# v0.net
KiCad netlist of a schematic drawn in EAGLE
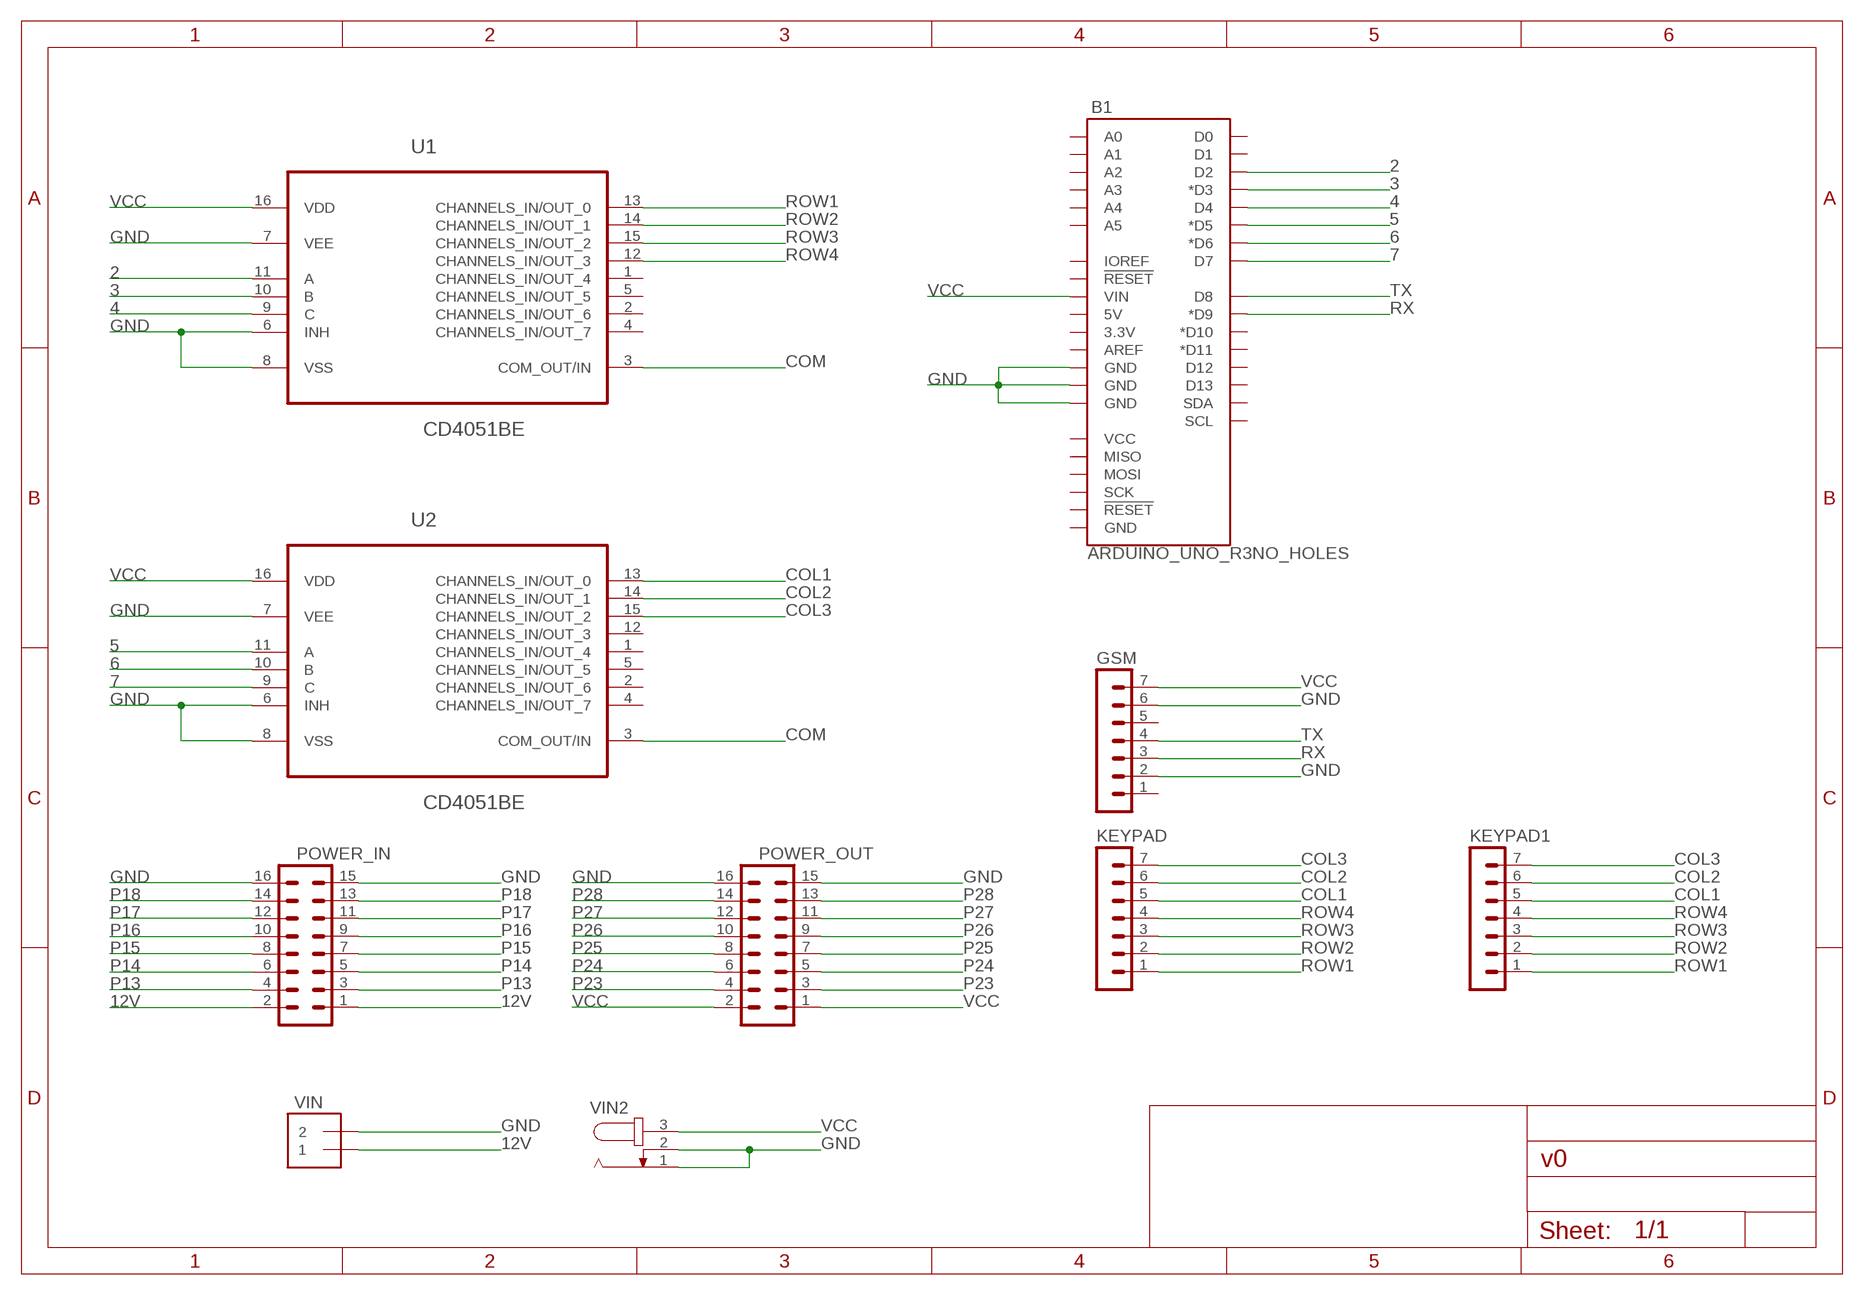
[diagram p0: schematic, sheet 1]

(export (version "E")
  (design (tool "Eeschema 10.0.6"))
  (components
    (comp (ref "B1")
      (value "ARDUINO_UNO_R3NO_HOLES")
      (footprint "eagle-import:ARDUINO_R3_NO_HOLES")
      (libsource (lib "eagle-import") (part "ARDUINO_UNO_R3NO_HOLES"))
    )
    (comp (ref "GSM")
      (value "MA07-1")
      (footprint "eagle-import:MA07-1")
      (libsource (lib "eagle-import") (part "MA07-1"))
    )
    (comp (ref "KEYPAD")
      (value "MA07-1")
      (footprint "eagle-import:MA07-1")
      (libsource (lib "eagle-import") (part "MA07-1"))
    )
    (comp (ref "KEYPAD1")
      (value "MA07-1")
      (footprint "eagle-import:MA07-1")
      (libsource (lib "eagle-import") (part "MA07-1"))
    )
    (comp (ref "POWER_IN")
      (value "MA08-2")
      (footprint "eagle-import:MA08-2")
      (libsource (lib "eagle-import") (part "MA08-2"))
    )
    (comp (ref "POWER_OUT")
      (value "MA08-2")
      (footprint "eagle-import:MA08-2")
      (libsource (lib "eagle-import") (part "MA08-2"))
    )
    (comp (ref "U1")
      (value "CD4051BE")
      (footprint "eagle-import:DIP254P762X508-16")
      (libsource (lib "eagle-import") (part "CD4051BE"))
    )
    (comp (ref "U2")
      (value "CD4051BE")
      (footprint "eagle-import:DIP254P762X508-16")
      (libsource (lib "eagle-import") (part "CD4051BE"))
    )
    (comp (ref "VIN")
      (value "1X2-3.5MM")
      (footprint "eagle-import:1X2-3.5MM")
      (libsource (lib "eagle-import") (part "1X2-3.5MM"))
    )
    (comp (ref "VIN2")
      (value "JACK-PLUG0")
      (footprint "eagle-import:SPC4077")
      (libsource (lib "eagle-import") (part "JACK-PLUG0"))
    )
  )
  (nets
    (net (code "1") (name "/2") (class "Default")
      (node (ref "B1") (pin "D2") (pinfunction "D2_D2") (pintype "bidirectional"))
      (node (ref "U1") (pin "11") (pinfunction "A_11") (pintype "input"))
    )
    (net (code "2") (name "/3") (class "Default")
      (node (ref "B1") (pin "D3") (pinfunction "*D3_D3") (pintype "bidirectional"))
      (node (ref "U1") (pin "10") (pinfunction "B_10") (pintype "input"))
    )
    (net (code "3") (name "/4") (class "Default")
      (node (ref "B1") (pin "D4") (pinfunction "D4_D4") (pintype "bidirectional"))
      (node (ref "U1") (pin "9") (pinfunction "C_9") (pintype "input"))
    )
    (net (code "4") (name "/5") (class "Default")
      (node (ref "B1") (pin "D5") (pinfunction "*D5_D5") (pintype "bidirectional"))
      (node (ref "U2") (pin "11") (pinfunction "A_11") (pintype "input"))
    )
    (net (code "5") (name "/6") (class "Default")
      (node (ref "B1") (pin "D6") (pinfunction "*D6_D6") (pintype "bidirectional"))
      (node (ref "U2") (pin "10") (pinfunction "B_10") (pintype "input"))
    )
    (net (code "6") (name "/7") (class "Default")
      (node (ref "B1") (pin "D7") (pinfunction "D7_D7") (pintype "bidirectional"))
      (node (ref "U2") (pin "9") (pinfunction "C_9") (pintype "input"))
    )
    (net (code "7") (name "/12V") (class "Default")
      (node (ref "POWER_IN") (pin "1") (pinfunction "1_1") (pintype "passive"))
      (node (ref "POWER_IN") (pin "2") (pinfunction "2_2") (pintype "passive"))
      (node (ref "VIN") (pin "1") (pinfunction "1_1") (pintype "passive"))
    )
    (net (code "8") (name "/COL1") (class "Default")
      (node (ref "KEYPAD") (pin "5") (pinfunction "5_5") (pintype "passive"))
      (node (ref "KEYPAD1") (pin "5") (pinfunction "5_5") (pintype "passive"))
      (node (ref "U2") (pin "13") (pinfunction "CHANNELS_IN/OUT_0_13") (pintype "bidirectional"))
    )
    (net (code "9") (name "/COL2") (class "Default")
      (node (ref "KEYPAD") (pin "6") (pinfunction "6_6") (pintype "passive"))
      (node (ref "KEYPAD1") (pin "6") (pinfunction "6_6") (pintype "passive"))
      (node (ref "U2") (pin "14") (pinfunction "CHANNELS_IN/OUT_1_14") (pintype "bidirectional"))
    )
    (net (code "10") (name "/COL3") (class "Default")
      (node (ref "KEYPAD") (pin "7") (pinfunction "7_7") (pintype "passive"))
      (node (ref "KEYPAD1") (pin "7") (pinfunction "7_7") (pintype "passive"))
      (node (ref "U2") (pin "15") (pinfunction "CHANNELS_IN/OUT_2_15") (pintype "bidirectional"))
    )
    (net (code "11") (name "/COM") (class "Default")
      (node (ref "U1") (pin "3") (pinfunction "COM_OUT/IN_3") (pintype "bidirectional"))
      (node (ref "U2") (pin "3") (pinfunction "COM_OUT/IN_3") (pintype "bidirectional"))
    )
    (net (code "12") (name "/GND") (class "Default")
      (node (ref "B1") (pin "GND@2") (pinfunction "GND_GND@2") (pintype "bidirectional"))
      (node (ref "B1") (pin "GND@3") (pinfunction "GND_GND@3") (pintype "bidirectional"))
      (node (ref "B1") (pin "GND@4") (pinfunction "GND_GND@4") (pintype "bidirectional"))
      (node (ref "GSM") (pin "2") (pinfunction "2_2") (pintype "passive"))
      (node (ref "GSM") (pin "6") (pinfunction "6_6") (pintype "passive"))
      (node (ref "POWER_IN") (pin "15") (pinfunction "15_15") (pintype "passive"))
      (node (ref "POWER_IN") (pin "16") (pinfunction "16_16") (pintype "passive"))
      (node (ref "POWER_OUT") (pin "15") (pinfunction "15_15") (pintype "passive"))
      (node (ref "POWER_OUT") (pin "16") (pinfunction "16_16") (pintype "passive"))
      (node (ref "U1") (pin "6") (pinfunction "INH_6") (pintype "input"))
      (node (ref "U1") (pin "7") (pinfunction "VEE_7") (pintype "power_in"))
      (node (ref "U1") (pin "8") (pinfunction "VSS_8") (pintype "power_in"))
      (node (ref "U2") (pin "6") (pinfunction "INH_6") (pintype "input"))
      (node (ref "U2") (pin "7") (pinfunction "VEE_7") (pintype "power_in"))
      (node (ref "U2") (pin "8") (pinfunction "VSS_8") (pintype "power_in"))
      (node (ref "VIN") (pin "2") (pinfunction "2_2") (pintype "passive"))
      (node (ref "VIN2") (pin "1") (pinfunction "1_1") (pintype "passive"))
      (node (ref "VIN2") (pin "2") (pinfunction "2_2") (pintype "passive"))
    )
    (net (code "13") (name "/P13") (class "Default")
      (node (ref "POWER_IN") (pin "3") (pinfunction "3_3") (pintype "passive"))
      (node (ref "POWER_IN") (pin "4") (pinfunction "4_4") (pintype "passive"))
    )
    (net (code "14") (name "/P14") (class "Default")
      (node (ref "POWER_IN") (pin "5") (pinfunction "5_5") (pintype "passive"))
      (node (ref "POWER_IN") (pin "6") (pinfunction "6_6") (pintype "passive"))
    )
    (net (code "15") (name "/P15") (class "Default")
      (node (ref "POWER_IN") (pin "7") (pinfunction "7_7") (pintype "passive"))
      (node (ref "POWER_IN") (pin "8") (pinfunction "8_8") (pintype "passive"))
    )
    (net (code "16") (name "/P16") (class "Default")
      (node (ref "POWER_IN") (pin "10") (pinfunction "10_10") (pintype "passive"))
      (node (ref "POWER_IN") (pin "9") (pinfunction "9_9") (pintype "passive"))
    )
    (net (code "17") (name "/P17") (class "Default")
      (node (ref "POWER_IN") (pin "11") (pinfunction "11_11") (pintype "passive"))
      (node (ref "POWER_IN") (pin "12") (pinfunction "12_12") (pintype "passive"))
    )
    (net (code "18") (name "/P18") (class "Default")
      (node (ref "POWER_IN") (pin "13") (pinfunction "13_13") (pintype "passive"))
      (node (ref "POWER_IN") (pin "14") (pinfunction "14_14") (pintype "passive"))
    )
    (net (code "19") (name "/P23") (class "Default")
      (node (ref "POWER_OUT") (pin "3") (pinfunction "3_3") (pintype "passive"))
      (node (ref "POWER_OUT") (pin "4") (pinfunction "4_4") (pintype "passive"))
    )
    (net (code "20") (name "/P24") (class "Default")
      (node (ref "POWER_OUT") (pin "5") (pinfunction "5_5") (pintype "passive"))
      (node (ref "POWER_OUT") (pin "6") (pinfunction "6_6") (pintype "passive"))
    )
    (net (code "21") (name "/P25") (class "Default")
      (node (ref "POWER_OUT") (pin "7") (pinfunction "7_7") (pintype "passive"))
      (node (ref "POWER_OUT") (pin "8") (pinfunction "8_8") (pintype "passive"))
    )
    (net (code "22") (name "/P26") (class "Default")
      (node (ref "POWER_OUT") (pin "10") (pinfunction "10_10") (pintype "passive"))
      (node (ref "POWER_OUT") (pin "9") (pinfunction "9_9") (pintype "passive"))
    )
    (net (code "23") (name "/P27") (class "Default")
      (node (ref "POWER_OUT") (pin "11") (pinfunction "11_11") (pintype "passive"))
      (node (ref "POWER_OUT") (pin "12") (pinfunction "12_12") (pintype "passive"))
    )
    (net (code "24") (name "/P28") (class "Default")
      (node (ref "POWER_OUT") (pin "13") (pinfunction "13_13") (pintype "passive"))
      (node (ref "POWER_OUT") (pin "14") (pinfunction "14_14") (pintype "passive"))
    )
    (net (code "25") (name "/ROW1") (class "Default")
      (node (ref "KEYPAD") (pin "1") (pinfunction "1_1") (pintype "passive"))
      (node (ref "KEYPAD1") (pin "1") (pinfunction "1_1") (pintype "passive"))
      (node (ref "U1") (pin "13") (pinfunction "CHANNELS_IN/OUT_0_13") (pintype "bidirectional"))
    )
    (net (code "26") (name "/ROW2") (class "Default")
      (node (ref "KEYPAD") (pin "2") (pinfunction "2_2") (pintype "passive"))
      (node (ref "KEYPAD1") (pin "2") (pinfunction "2_2") (pintype "passive"))
      (node (ref "U1") (pin "14") (pinfunction "CHANNELS_IN/OUT_1_14") (pintype "bidirectional"))
    )
    (net (code "27") (name "/ROW3") (class "Default")
      (node (ref "KEYPAD") (pin "3") (pinfunction "3_3") (pintype "passive"))
      (node (ref "KEYPAD1") (pin "3") (pinfunction "3_3") (pintype "passive"))
      (node (ref "U1") (pin "15") (pinfunction "CHANNELS_IN/OUT_2_15") (pintype "bidirectional"))
    )
    (net (code "28") (name "/ROW4") (class "Default")
      (node (ref "KEYPAD") (pin "4") (pinfunction "4_4") (pintype "passive"))
      (node (ref "KEYPAD1") (pin "4") (pinfunction "4_4") (pintype "passive"))
      (node (ref "U1") (pin "12") (pinfunction "CHANNELS_IN/OUT_3_12") (pintype "bidirectional"))
    )
    (net (code "29") (name "/RX") (class "Default")
      (node (ref "B1") (pin "D9") (pinfunction "*D9_D9") (pintype "bidirectional"))
      (node (ref "GSM") (pin "3") (pinfunction "3_3") (pintype "passive"))
    )
    (net (code "30") (name "/TX") (class "Default")
      (node (ref "B1") (pin "D8") (pinfunction "D8_D8") (pintype "bidirectional"))
      (node (ref "GSM") (pin "4") (pinfunction "4_4") (pintype "passive"))
    )
    (net (code "31") (name "/VCC") (class "Default")
      (node (ref "B1") (pin "VIN") (pinfunction "VIN_VIN") (pintype "bidirectional"))
      (node (ref "GSM") (pin "7") (pinfunction "7_7") (pintype "passive"))
      (node (ref "POWER_OUT") (pin "1") (pinfunction "1_1") (pintype "passive"))
      (node (ref "POWER_OUT") (pin "2") (pinfunction "2_2") (pintype "passive"))
      (node (ref "U1") (pin "16") (pinfunction "VDD_16") (pintype "power_in"))
      (node (ref "U2") (pin "16") (pinfunction "VDD_16") (pintype "power_in"))
      (node (ref "VIN2") (pin "3") (pinfunction "3_3") (pintype "passive"))
    )
    (net (code "32") (name "unconnected-(B1-*D10-PadD10)") (class "Default")
      (node (ref "B1") (pin "D10") (pinfunction "*D10_D10") (pintype "bidirectional"))
    )
    (net (code "33") (name "unconnected-(B1-*D11-PadD11)") (class "Default")
      (node (ref "B1") (pin "D11") (pinfunction "*D11_D11") (pintype "bidirectional"))
    )
    (net (code "34") (name "unconnected-(B1-GND-PadGND@1)") (class "Default")
      (node (ref "B1") (pin "GND@1") (pinfunction "GND_GND@1") (pintype "bidirectional"))
    )
    (net (code "35") (name "unconnected-(B1-Pad3.3V)") (class "Default")
      (node (ref "B1") (pin "3.3V") (pinfunction "3.3V_3.3V") (pintype "bidirectional"))
    )
    (net (code "36") (name "unconnected-(B1-Pad5V)") (class "Default")
      (node (ref "B1") (pin "5V") (pinfunction "5V_5V") (pintype "bidirectional"))
    )
    (net (code "37") (name "unconnected-(B1-PadA0)") (class "Default")
      (node (ref "B1") (pin "A0") (pinfunction "A0_A0") (pintype "bidirectional"))
    )
    (net (code "38") (name "unconnected-(B1-PadA1)") (class "Default")
      (node (ref "B1") (pin "A1") (pinfunction "A1_A1") (pintype "bidirectional"))
    )
    (net (code "39") (name "unconnected-(B1-PadA2)") (class "Default")
      (node (ref "B1") (pin "A2") (pinfunction "A2_A2") (pintype "bidirectional"))
    )
    (net (code "40") (name "unconnected-(B1-PadA3)") (class "Default")
      (node (ref "B1") (pin "A3") (pinfunction "A3_A3") (pintype "bidirectional"))
    )
    (net (code "41") (name "unconnected-(B1-PadA4)") (class "Default")
      (node (ref "B1") (pin "A4") (pinfunction "A4_A4") (pintype "bidirectional"))
    )
    (net (code "42") (name "unconnected-(B1-PadA5)") (class "Default")
      (node (ref "B1") (pin "A5") (pinfunction "A5_A5") (pintype "bidirectional"))
    )
    (net (code "43") (name "unconnected-(B1-PadAREF)") (class "Default")
      (node (ref "B1") (pin "AREF") (pinfunction "AREF_AREF") (pintype "bidirectional"))
    )
    (net (code "44") (name "unconnected-(B1-PadD0)") (class "Default")
      (node (ref "B1") (pin "D0") (pinfunction "D0_D0") (pintype "bidirectional"))
    )
    (net (code "45") (name "unconnected-(B1-PadD1)") (class "Default")
      (node (ref "B1") (pin "D1") (pinfunction "D1_D1") (pintype "bidirectional"))
    )
    (net (code "46") (name "unconnected-(B1-PadD12)") (class "Default")
      (node (ref "B1") (pin "D12") (pinfunction "D12_D12") (pintype "bidirectional"))
    )
    (net (code "47") (name "unconnected-(B1-PadD13)") (class "Default")
      (node (ref "B1") (pin "D13") (pinfunction "D13_D13") (pintype "bidirectional"))
    )
    (net (code "48") (name "unconnected-(B1-PadIOREF)") (class "Default")
      (node (ref "B1") (pin "IOREF") (pinfunction "IOREF_IOREF") (pintype "bidirectional"))
    )
    (net (code "49") (name "unconnected-(B1-PadMISO)") (class "Default")
      (node (ref "B1") (pin "MISO") (pinfunction "MISO_MISO") (pintype "bidirectional"))
    )
    (net (code "50") (name "unconnected-(B1-PadMOSI)") (class "Default")
      (node (ref "B1") (pin "MOSI") (pinfunction "MOSI_MOSI") (pintype "bidirectional"))
    )
    (net (code "51") (name "unconnected-(B1-PadSCK)") (class "Default")
      (node (ref "B1") (pin "SCK") (pinfunction "SCK_SCK") (pintype "bidirectional"))
    )
    (net (code "52") (name "unconnected-(B1-PadSCL)") (class "Default")
      (node (ref "B1") (pin "SCL") (pinfunction "SCL_SCL") (pintype "bidirectional"))
    )
    (net (code "53") (name "unconnected-(B1-PadSDA)") (class "Default")
      (node (ref "B1") (pin "SDA") (pinfunction "SDA_SDA") (pintype "bidirectional"))
    )
    (net (code "54") (name "unconnected-(B1-PadVCC)") (class "Default")
      (node (ref "B1") (pin "VCC") (pinfunction "VCC_VCC") (pintype "bidirectional"))
    )
    (net (code "55") (name "unconnected-(B1-~{RESET}-PadRESET@1)") (class "Default")
      (node (ref "B1") (pin "RESET@1") (pinfunction "~{RESET}_RESET@1") (pintype "bidirectional"))
    )
    (net (code "56") (name "unconnected-(B1-~{RESET}-PadRESET@2)") (class "Default")
      (node (ref "B1") (pin "RESET@2") (pinfunction "~{RESET}_RESET@2") (pintype "bidirectional"))
    )
    (net (code "57") (name "unconnected-(GSM-Pad1)") (class "Default")
      (node (ref "GSM") (pin "1") (pinfunction "1_1") (pintype "passive"))
    )
    (net (code "58") (name "unconnected-(GSM-Pad5)") (class "Default")
      (node (ref "GSM") (pin "5") (pinfunction "5_5") (pintype "passive"))
    )
    (net (code "59") (name "unconnected-(U1-CHANNELS_IN{slash}OUT_4-Pad1)") (class "Default")
      (node (ref "U1") (pin "1") (pinfunction "CHANNELS_IN/OUT_4_1") (pintype "bidirectional"))
    )
    (net (code "60") (name "unconnected-(U1-CHANNELS_IN{slash}OUT_5-Pad5)") (class "Default")
      (node (ref "U1") (pin "5") (pinfunction "CHANNELS_IN/OUT_5_5") (pintype "bidirectional"))
    )
    (net (code "61") (name "unconnected-(U1-CHANNELS_IN{slash}OUT_6-Pad2)") (class "Default")
      (node (ref "U1") (pin "2") (pinfunction "CHANNELS_IN/OUT_6_2") (pintype "bidirectional"))
    )
    (net (code "62") (name "unconnected-(U1-CHANNELS_IN{slash}OUT_7-Pad4)") (class "Default")
      (node (ref "U1") (pin "4") (pinfunction "CHANNELS_IN/OUT_7_4") (pintype "bidirectional"))
    )
    (net (code "63") (name "unconnected-(U2-CHANNELS_IN{slash}OUT_3-Pad12)") (class "Default")
      (node (ref "U2") (pin "12") (pinfunction "CHANNELS_IN/OUT_3_12") (pintype "bidirectional"))
    )
    (net (code "64") (name "unconnected-(U2-CHANNELS_IN{slash}OUT_4-Pad1)") (class "Default")
      (node (ref "U2") (pin "1") (pinfunction "CHANNELS_IN/OUT_4_1") (pintype "bidirectional"))
    )
    (net (code "65") (name "unconnected-(U2-CHANNELS_IN{slash}OUT_5-Pad5)") (class "Default")
      (node (ref "U2") (pin "5") (pinfunction "CHANNELS_IN/OUT_5_5") (pintype "bidirectional"))
    )
    (net (code "66") (name "unconnected-(U2-CHANNELS_IN{slash}OUT_6-Pad2)") (class "Default")
      (node (ref "U2") (pin "2") (pinfunction "CHANNELS_IN/OUT_6_2") (pintype "bidirectional"))
    )
    (net (code "67") (name "unconnected-(U2-CHANNELS_IN{slash}OUT_7-Pad4)") (class "Default")
      (node (ref "U2") (pin "4") (pinfunction "CHANNELS_IN/OUT_7_4") (pintype "bidirectional"))
    )
  )
)
